# clock_schematic.net
KiCad netlist of a schematic drawn in EAGLE
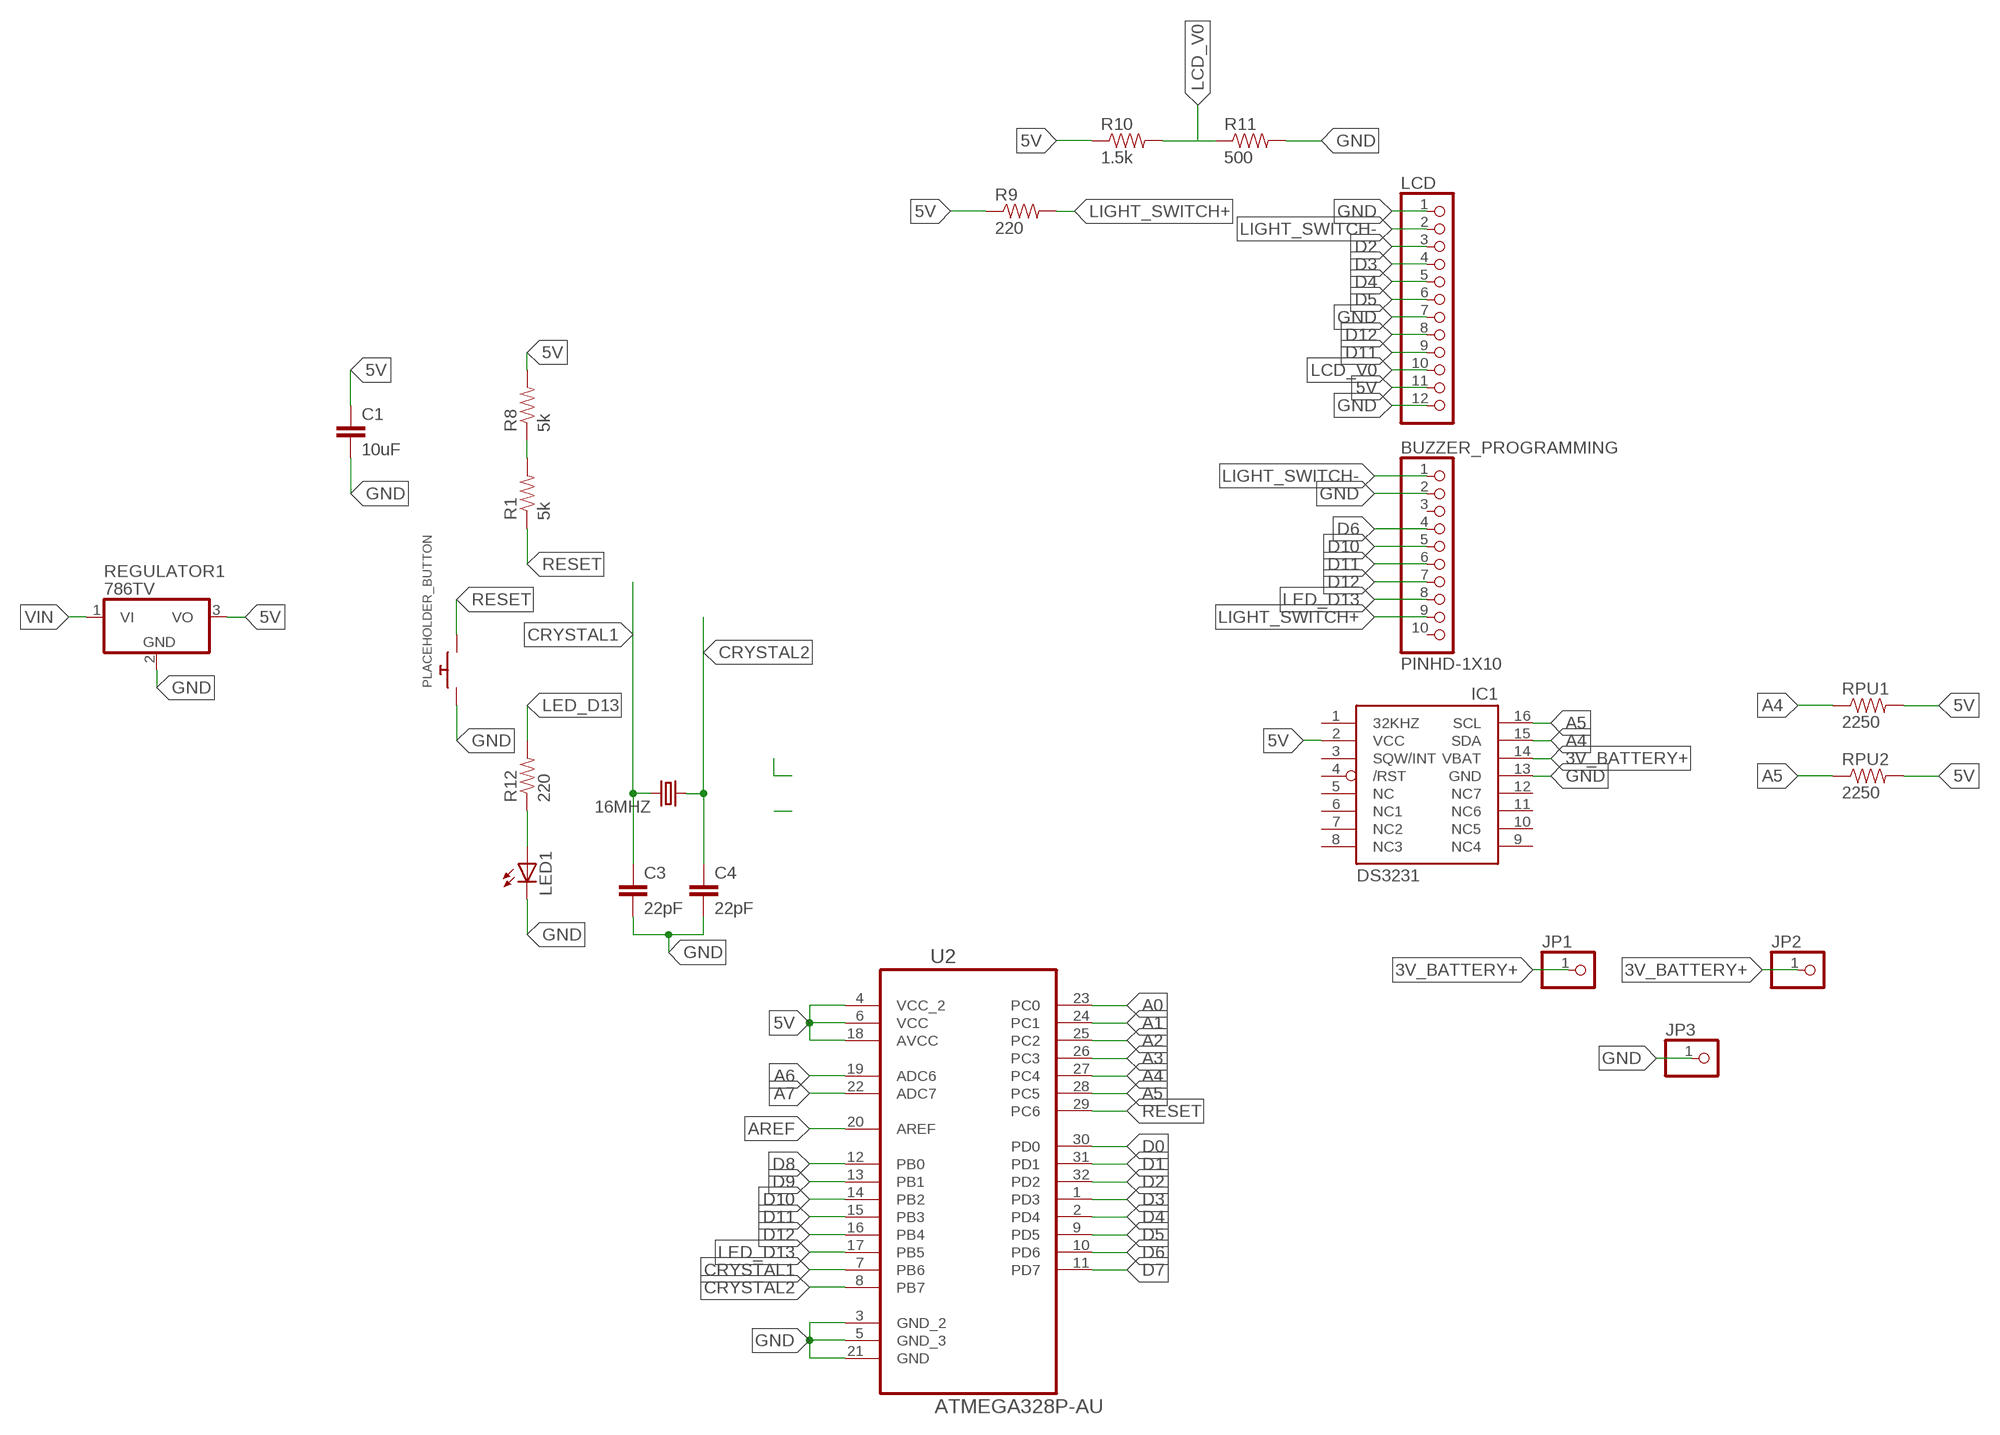
[diagram p0: schematic, sheet 1]

(export (version "E")
  (design (tool "Eeschema 10.0.6"))
  (components
    (comp (ref "16MHZ")
      (value "CRYSTALHC18U-V")
      (footprint "eagle-import:HC18U-V")
      (libsource (lib "eagle-import") (part "CRYSTALHC18U-V"))
    )
    (comp (ref "BUZZER_PROGRAMMING")
      (value "PINHD-1X10")
      (footprint "eagle-import:1X10-BIG")
      (libsource (lib "eagle-import") (part "PINHD-1X10"))
    )
    (comp (ref "C1")
      (value "10uF")
      (footprint "eagle-import:0805")
      (libsource (lib "eagle-import") (part "CAP0805"))
    )
    (comp (ref "C3")
      (value "22pF")
      (footprint "eagle-import:0805")
      (libsource (lib "eagle-import") (part "CAP0805"))
    )
    (comp (ref "C4")
      (value "22pF")
      (footprint "eagle-import:0805")
      (libsource (lib "eagle-import") (part "CAP0805"))
    )
    (comp (ref "IC1")
      (value "DS3231/SO")
      (footprint "eagle-import:SO16W")
      (libsource (lib "eagle-import") (part "DS3231/SO"))
    )
    (comp (ref "JP1")
      (value "PINHD-1X1")
      (footprint "eagle-import:1X01")
      (libsource (lib "eagle-import") (part "PINHD-1X1"))
    )
    (comp (ref "JP2")
      (value "PINHD-1X1")
      (footprint "eagle-import:1X01")
      (libsource (lib "eagle-import") (part "PINHD-1X1"))
    )
    (comp (ref "JP3")
      (value "PINHD-1X1")
      (footprint "eagle-import:1X01")
      (libsource (lib "eagle-import") (part "PINHD-1X1"))
    )
    (comp (ref "LCD")
      (value "PINHD-1X12")
      (footprint "eagle-import:1X12")
      (libsource (lib "eagle-import") (part "PINHD-1X12"))
    )
    (comp (ref "LED1")
      (value "LEDCHIPLED_0805")
      (footprint "eagle-import:CHIPLED_0805")
      (libsource (lib "eagle-import") (part "LEDCHIPLED_0805"))
    )
    (comp (ref "PLACEHOLDER_BUTTON")
      (value "SWITCH_PUSHBUTTONSOFTTOUCHSMD_SJ")
      (footprint "eagle-import:PUSHBUTTON_SMD_SJ")
      (libsource (lib "eagle-import") (part "SWITCH_PUSHBUTTONSOFTTOUCHSMD_SJ"))
    )
    (comp (ref "R1")
      (value "5k")
      (footprint "eagle-import:0805")
      (libsource (lib "eagle-import") (part "RESISTOR0805-RES"))
    )
    (comp (ref "R8")
      (value "5k")
      (footprint "eagle-import:0805")
      (libsource (lib "eagle-import") (part "RESISTOR0805-RES"))
    )
    (comp (ref "R9")
      (value "220")
      (footprint "eagle-import:0805")
      (libsource (lib "eagle-import") (part "RESISTOR0805-RES"))
    )
    (comp (ref "R10")
      (value "1.5k")
      (footprint "eagle-import:0805")
      (libsource (lib "eagle-import") (part "RESISTOR0805-RES"))
    )
    (comp (ref "R11")
      (value "500")
      (footprint "eagle-import:0805")
      (libsource (lib "eagle-import") (part "RESISTOR0805-RES"))
    )
    (comp (ref "R12")
      (value "220")
      (footprint "eagle-import:0805")
      (libsource (lib "eagle-import") (part "RESISTOR0805-RES"))
    )
    (comp (ref "REGULATOR1")
      (value "786TV")
      (footprint "eagle-import:TO220V")
      (libsource (lib "eagle-import") (part "78TV6"))
    )
    (comp (ref "RPU1")
      (value "2250")
      (footprint "eagle-import:0805")
      (libsource (lib "eagle-import") (part "RESISTOR0805-RES"))
    )
    (comp (ref "RPU2")
      (value "2250")
      (footprint "eagle-import:0805")
      (libsource (lib "eagle-import") (part "RESISTOR0805-RES"))
    )
    (comp (ref "U2")
      (value "ATMEGA328P-AU")
      (footprint "eagle-import:QFP80P900X900X120-32N")
      (libsource (lib "eagle-import") (part "ATMEGA328P-AU"))
    )
  )
  (nets
    (net (code "1") (name "3V_BATTERY+") (class "Default")
      (node (ref "IC1") (pin "14") (pinfunction "VBAT_14") (pintype "power_in"))
      (node (ref "JP1") (pin "1") (pinfunction "1_1") (pintype "passive"))
      (node (ref "JP2") (pin "1") (pinfunction "1_1") (pintype "passive"))
    )
    (net (code "2") (name "5V") (class "Default")
      (node (ref "C1") (pin "1") (pinfunction "1_1") (pintype "passive"))
      (node (ref "IC1") (pin "2") (pinfunction "VCC_2") (pintype "power_in"))
      (node (ref "LCD") (pin "11") (pinfunction "11_11") (pintype "passive"))
      (node (ref "R10") (pin "1") (pinfunction "1_1") (pintype "passive"))
      (node (ref "R8") (pin "2") (pinfunction "2_2") (pintype "passive"))
      (node (ref "R9") (pin "1") (pinfunction "1_1") (pintype "passive"))
      (node (ref "REGULATOR1") (pin "3") (pinfunction "VO_3") (pintype "passive"))
      (node (ref "RPU1") (pin "2") (pinfunction "2_2") (pintype "passive"))
      (node (ref "RPU2") (pin "2") (pinfunction "2_2") (pintype "passive"))
      (node (ref "U2") (pin "18") (pinfunction "AVCC_18") (pintype "power_in"))
      (node (ref "U2") (pin "4") (pinfunction "VCC_2_4") (pintype "power_in"))
      (node (ref "U2") (pin "6") (pinfunction "VCC_6") (pintype "power_in"))
    )
    (net (code "3") (name "A0") (class "Default")
      (node (ref "U2") (pin "23") (pinfunction "PC0_23") (pintype "bidirectional"))
    )
    (net (code "4") (name "A1") (class "Default")
      (node (ref "U2") (pin "24") (pinfunction "PC1_24") (pintype "bidirectional"))
    )
    (net (code "5") (name "A2") (class "Default")
      (node (ref "U2") (pin "25") (pinfunction "PC2_25") (pintype "bidirectional"))
    )
    (net (code "6") (name "A3") (class "Default")
      (node (ref "U2") (pin "26") (pinfunction "PC3_26") (pintype "bidirectional"))
    )
    (net (code "7") (name "A4") (class "Default")
      (node (ref "IC1") (pin "15") (pinfunction "SDA_15") (pintype "bidirectional"))
      (node (ref "RPU1") (pin "1") (pinfunction "1_1") (pintype "passive"))
      (node (ref "U2") (pin "27") (pinfunction "PC4_27") (pintype "bidirectional"))
    )
    (net (code "8") (name "A5") (class "Default")
      (node (ref "IC1") (pin "16") (pinfunction "SCL_16") (pintype "bidirectional"))
      (node (ref "RPU2") (pin "1") (pinfunction "1_1") (pintype "passive"))
      (node (ref "U2") (pin "28") (pinfunction "PC5_28") (pintype "bidirectional"))
    )
    (net (code "9") (name "A6") (class "Default")
      (node (ref "U2") (pin "19") (pinfunction "ADC6_19") (pintype "input"))
    )
    (net (code "10") (name "A7") (class "Default")
      (node (ref "U2") (pin "22") (pinfunction "ADC7_22") (pintype "input"))
    )
    (net (code "11") (name "AREF") (class "Default")
      (node (ref "U2") (pin "20") (pinfunction "AREF_20") (pintype "input"))
    )
    (net (code "12") (name "CRYSTAL1") (class "Default")
      (node (ref "16MHZ") (pin "2") (pinfunction "2_2") (pintype "passive"))
      (node (ref "C3") (pin "1") (pinfunction "1_1") (pintype "passive"))
      (node (ref "U2") (pin "7") (pinfunction "PB6_7") (pintype "bidirectional"))
    )
    (net (code "13") (name "CRYSTAL2") (class "Default")
      (node (ref "16MHZ") (pin "1") (pinfunction "1_1") (pintype "passive"))
      (node (ref "C4") (pin "1") (pinfunction "1_1") (pintype "passive"))
      (node (ref "U2") (pin "8") (pinfunction "PB7_8") (pintype "bidirectional"))
    )
    (net (code "14") (name "D0") (class "Default")
      (node (ref "U2") (pin "30") (pinfunction "PD0_30") (pintype "bidirectional"))
    )
    (net (code "15") (name "D1") (class "Default")
      (node (ref "U2") (pin "31") (pinfunction "PD1_31") (pintype "bidirectional"))
    )
    (net (code "16") (name "D2") (class "Default")
      (node (ref "LCD") (pin "3") (pinfunction "3_3") (pintype "passive"))
      (node (ref "U2") (pin "32") (pinfunction "PD2_32") (pintype "bidirectional"))
    )
    (net (code "17") (name "D3") (class "Default")
      (node (ref "LCD") (pin "4") (pinfunction "4_4") (pintype "passive"))
      (node (ref "U2") (pin "1") (pinfunction "PD3_1") (pintype "bidirectional"))
    )
    (net (code "18") (name "D4") (class "Default")
      (node (ref "LCD") (pin "5") (pinfunction "5_5") (pintype "passive"))
      (node (ref "U2") (pin "2") (pinfunction "PD4_2") (pintype "bidirectional"))
    )
    (net (code "19") (name "D5") (class "Default")
      (node (ref "LCD") (pin "6") (pinfunction "6_6") (pintype "passive"))
      (node (ref "U2") (pin "9") (pinfunction "PD5_9") (pintype "bidirectional"))
    )
    (net (code "20") (name "D6") (class "Default")
      (node (ref "BUZZER_PROGRAMMING") (pin "4") (pinfunction "4_4") (pintype "passive"))
      (node (ref "U2") (pin "10") (pinfunction "PD6_10") (pintype "bidirectional"))
    )
    (net (code "21") (name "D7") (class "Default")
      (node (ref "U2") (pin "11") (pinfunction "PD7_11") (pintype "bidirectional"))
    )
    (net (code "22") (name "D8") (class "Default")
      (node (ref "U2") (pin "12") (pinfunction "PB0_12") (pintype "bidirectional"))
    )
    (net (code "23") (name "D9") (class "Default")
      (node (ref "U2") (pin "13") (pinfunction "PB1_13") (pintype "bidirectional"))
    )
    (net (code "24") (name "D10") (class "Default")
      (node (ref "BUZZER_PROGRAMMING") (pin "5") (pinfunction "5_5") (pintype "passive"))
      (node (ref "U2") (pin "14") (pinfunction "PB2_14") (pintype "bidirectional"))
    )
    (net (code "25") (name "D11") (class "Default")
      (node (ref "BUZZER_PROGRAMMING") (pin "6") (pinfunction "6_6") (pintype "passive"))
      (node (ref "LCD") (pin "9") (pinfunction "9_9") (pintype "passive"))
      (node (ref "U2") (pin "15") (pinfunction "PB3_15") (pintype "bidirectional"))
    )
    (net (code "26") (name "D12") (class "Default")
      (node (ref "BUZZER_PROGRAMMING") (pin "7") (pinfunction "7_7") (pintype "passive"))
      (node (ref "LCD") (pin "8") (pinfunction "8_8") (pintype "passive"))
      (node (ref "U2") (pin "16") (pinfunction "PB4_16") (pintype "bidirectional"))
    )
    (net (code "27") (name "GND") (class "Default")
      (node (ref "BUZZER_PROGRAMMING") (pin "2") (pinfunction "2_2") (pintype "passive"))
      (node (ref "C1") (pin "2") (pinfunction "2_2") (pintype "passive"))
      (node (ref "C3") (pin "2") (pinfunction "2_2") (pintype "passive"))
      (node (ref "C4") (pin "2") (pinfunction "2_2") (pintype "passive"))
      (node (ref "IC1") (pin "13") (pinfunction "GND_13") (pintype "power_in"))
      (node (ref "JP3") (pin "1") (pinfunction "1_1") (pintype "passive"))
      (node (ref "LCD") (pin "1") (pinfunction "1_1") (pintype "passive"))
      (node (ref "LCD") (pin "12") (pinfunction "12_12") (pintype "passive"))
      (node (ref "LCD") (pin "7") (pinfunction "7_7") (pintype "passive"))
      (node (ref "LED1") (pin "C") (pinfunction "C_C") (pintype "passive"))
      (node (ref "PLACEHOLDER_BUTTON") (pin "P$1") (pinfunction "P$1_P$1") (pintype "passive"))
      (node (ref "R11") (pin "2") (pinfunction "2_2") (pintype "passive"))
      (node (ref "REGULATOR1") (pin "2") (pinfunction "GND_2") (pintype "passive"))
      (node (ref "U2") (pin "21") (pinfunction "GND_21") (pintype "passive"))
      (node (ref "U2") (pin "3") (pinfunction "GND_2_3") (pintype "passive"))
      (node (ref "U2") (pin "5") (pinfunction "GND_3_5") (pintype "passive"))
    )
    (net (code "28") (name "LCD_V0") (class "Default")
      (node (ref "LCD") (pin "10") (pinfunction "10_10") (pintype "passive"))
      (node (ref "R10") (pin "2") (pinfunction "2_2") (pintype "passive"))
      (node (ref "R11") (pin "1") (pinfunction "1_1") (pintype "passive"))
    )
    (net (code "29") (name "LED_D13") (class "Default")
      (node (ref "BUZZER_PROGRAMMING") (pin "8") (pinfunction "8_8") (pintype "passive"))
      (node (ref "R12") (pin "2") (pinfunction "2_2") (pintype "passive"))
      (node (ref "U2") (pin "17") (pinfunction "PB5_17") (pintype "bidirectional"))
    )
    (net (code "30") (name "LIGHT_SWITCH+") (class "Default")
      (node (ref "BUZZER_PROGRAMMING") (pin "9") (pinfunction "9_9") (pintype "passive"))
      (node (ref "R9") (pin "2") (pinfunction "2_2") (pintype "passive"))
    )
    (net (code "31") (name "LIGHT_SWITCH-") (class "Default")
      (node (ref "BUZZER_PROGRAMMING") (pin "1") (pinfunction "1_1") (pintype "passive"))
      (node (ref "LCD") (pin "2") (pinfunction "2_2") (pintype "passive"))
    )
    (net (code "32") (name "Net-(LED1-PadA)") (class "Default")
      (node (ref "LED1") (pin "A") (pinfunction "A_A") (pintype "passive"))
      (node (ref "R12") (pin "1") (pinfunction "1_1") (pintype "passive"))
    )
    (net (code "33") (name "Net-(R1-Pad2)") (class "Default")
      (node (ref "R1") (pin "2") (pinfunction "2_2") (pintype "passive"))
      (node (ref "R8") (pin "1") (pinfunction "1_1") (pintype "passive"))
    )
    (net (code "34") (name "RESET") (class "Default")
      (node (ref "PLACEHOLDER_BUTTON") (pin "P$2") (pinfunction "P$2_P$2") (pintype "passive"))
      (node (ref "R1") (pin "1") (pinfunction "1_1") (pintype "passive"))
      (node (ref "U2") (pin "29") (pinfunction "PC6_29") (pintype "bidirectional"))
    )
    (net (code "35") (name "VIN") (class "Default")
      (node (ref "REGULATOR1") (pin "1") (pinfunction "VI_1") (pintype "input"))
    )
    (net (code "36") (name "unconnected-(BUZZER_PROGRAMMING-Pad3)") (class "Default")
      (node (ref "BUZZER_PROGRAMMING") (pin "3") (pinfunction "3_3") (pintype "passive"))
    )
    (net (code "37") (name "unconnected-(BUZZER_PROGRAMMING-Pad10)") (class "Default")
      (node (ref "BUZZER_PROGRAMMING") (pin "10") (pinfunction "10_10") (pintype "passive"))
    )
    (net (code "38") (name "unconnected-(IC1-32KHZ-Pad1)") (class "Default")
      (node (ref "IC1") (pin "1") (pinfunction "32KHZ_1") (pintype "output"))
    )
    (net (code "39") (name "unconnected-(IC1-NC-Pad5)") (class "Default")
      (node (ref "IC1") (pin "5") (pinfunction "NC_5") (pintype "no_connect"))
    )
    (net (code "40") (name "unconnected-(IC1-NC1-Pad6)") (class "Default")
      (node (ref "IC1") (pin "6") (pinfunction "NC1_6") (pintype "no_connect"))
    )
    (net (code "41") (name "unconnected-(IC1-NC2-Pad7)") (class "Default")
      (node (ref "IC1") (pin "7") (pinfunction "NC2_7") (pintype "no_connect"))
    )
    (net (code "42") (name "unconnected-(IC1-NC3-Pad8)") (class "Default")
      (node (ref "IC1") (pin "8") (pinfunction "NC3_8") (pintype "no_connect"))
    )
    (net (code "43") (name "unconnected-(IC1-NC4-Pad9)") (class "Default")
      (node (ref "IC1") (pin "9") (pinfunction "NC4_9") (pintype "no_connect"))
    )
    (net (code "44") (name "unconnected-(IC1-NC5-Pad10)") (class "Default")
      (node (ref "IC1") (pin "10") (pinfunction "NC5_10") (pintype "no_connect"))
    )
    (net (code "45") (name "unconnected-(IC1-NC6-Pad11)") (class "Default")
      (node (ref "IC1") (pin "11") (pinfunction "NC6_11") (pintype "no_connect"))
    )
    (net (code "46") (name "unconnected-(IC1-NC7-Pad12)") (class "Default")
      (node (ref "IC1") (pin "12") (pinfunction "NC7_12") (pintype "no_connect"))
    )
    (net (code "47") (name "unconnected-(IC1-SQW{slash}INT-Pad3)") (class "Default")
      (node (ref "IC1") (pin "3") (pinfunction "SQW/INT_3") (pintype "output"))
    )
    (net (code "48") (name "unconnected-(IC1-{slash}RST-Pad4)") (class "Default")
      (node (ref "IC1") (pin "4") (pinfunction "/RST_4") (pintype "passive"))
    )
  )
)
